# ISM4319.net
KiCad netlist of a schematic drawn in Altium Designer
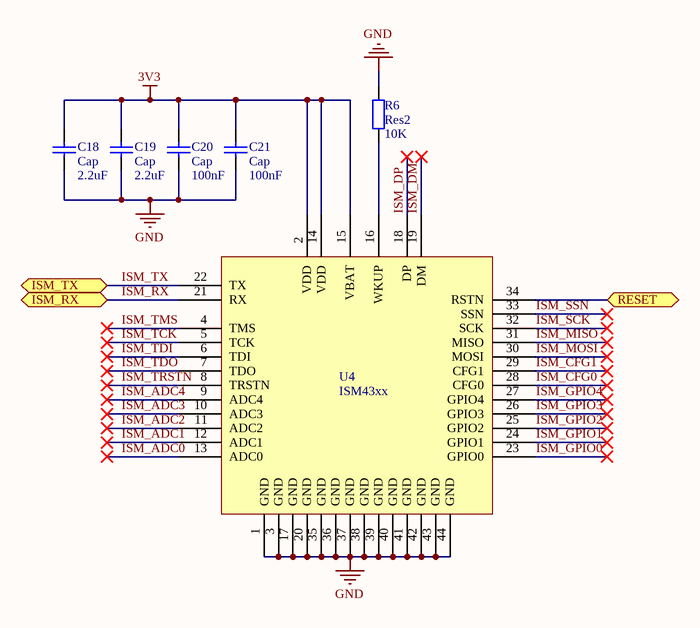
[diagram p0: ISM4319.SchDoc]

(export (version "E")
  (design (tool "Eeschema 10.0.6"))
  (components
    (comp (ref "C18")
      (value "Cap")
      (footprint "0603")
      (description "Capacitor")
      (fields (field (name "ALTIUM_VALUE") "2.2uF"))
      (libsource (lib "Miscellaneous Devices") (part "Cap"))
    )
    (comp (ref "C19")
      (value "Cap")
      (footprint "0603")
      (description "Capacitor")
      (fields (field (name "ALTIUM_VALUE") "2.2uF"))
      (libsource (lib "Miscellaneous Devices") (part "Cap"))
    )
    (comp (ref "C20")
      (value "Cap")
      (footprint "0603")
      (description "Capacitor")
      (fields (field (name "ALTIUM_VALUE") "100nF"))
      (libsource (lib "Miscellaneous Devices") (part "Cap"))
    )
    (comp (ref "C21")
      (value "Cap")
      (footprint "0603")
      (description "Capacitor")
      (fields (field (name "ALTIUM_VALUE") "100nF"))
      (libsource (lib "Miscellaneous Devices") (part "Cap"))
    )
    (comp (ref "R6")
      (value "Res2")
      (footprint "0603")
      (description "Resistor")
      (fields (field (name "ALTIUM_VALUE") "10K"))
      (libsource (lib "Miscellaneous Devices") (part "Res2"))
    )
    (comp (ref "U4")
      (value "ISM43xx")
      (footprint "ISM-WIFI")
      (description "Inventek Systems WiFi Module")
      (libsource (lib "BrewBit") (part "ISM4319"))
    )
  )
  (nets
    (net (code "1") (name "/ISM_ADC0") (class "Default")
      (node (ref "U4") (pin "13") (pinfunction "ADC0_13") (pintype "passive+no_connect"))
    )
    (net (code "2") (name "/ISM_ADC1") (class "Default")
      (node (ref "U4") (pin "12") (pinfunction "ADC1_12") (pintype "passive+no_connect"))
    )
    (net (code "3") (name "/ISM_ADC2") (class "Default")
      (node (ref "U4") (pin "11") (pinfunction "ADC2_11") (pintype "passive+no_connect"))
    )
    (net (code "4") (name "/ISM_ADC3") (class "Default")
      (node (ref "U4") (pin "10") (pinfunction "ADC3_10") (pintype "passive+no_connect"))
    )
    (net (code "5") (name "/ISM_ADC4") (class "Default")
      (node (ref "U4") (pin "9") (pinfunction "ADC4_9") (pintype "passive+no_connect"))
    )
    (net (code "6") (name "/ISM_CFG0") (class "Default")
      (node (ref "U4") (pin "28") (pinfunction "CFG0_28") (pintype "passive+no_connect"))
    )
    (net (code "7") (name "/ISM_CFG1") (class "Default")
      (node (ref "U4") (pin "29") (pinfunction "CFG1_29") (pintype "passive+no_connect"))
    )
    (net (code "8") (name "/ISM_DM") (class "Default")
      (node (ref "U4") (pin "19") (pinfunction "DM_19") (pintype "passive+no_connect"))
    )
    (net (code "9") (name "/ISM_DP") (class "Default")
      (node (ref "U4") (pin "18") (pinfunction "DP_18") (pintype "passive+no_connect"))
    )
    (net (code "10") (name "/ISM_GPIO0") (class "Default")
      (node (ref "U4") (pin "23") (pinfunction "GPIO0_23") (pintype "passive+no_connect"))
    )
    (net (code "11") (name "/ISM_GPIO1") (class "Default")
      (node (ref "U4") (pin "24") (pinfunction "GPIO1_24") (pintype "passive+no_connect"))
    )
    (net (code "12") (name "/ISM_GPIO2") (class "Default")
      (node (ref "U4") (pin "25") (pinfunction "GPIO2_25") (pintype "passive+no_connect"))
    )
    (net (code "13") (name "/ISM_GPIO3") (class "Default")
      (node (ref "U4") (pin "26") (pinfunction "GPIO3_26") (pintype "passive+no_connect"))
    )
    (net (code "14") (name "/ISM_GPIO4") (class "Default")
      (node (ref "U4") (pin "27") (pinfunction "GPIO4_27") (pintype "passive+no_connect"))
    )
    (net (code "15") (name "/ISM_MISO") (class "Default")
      (node (ref "U4") (pin "31") (pinfunction "MISO_31") (pintype "passive+no_connect"))
    )
    (net (code "16") (name "/ISM_MOSI") (class "Default")
      (node (ref "U4") (pin "30") (pinfunction "MOSI_30") (pintype "passive+no_connect"))
    )
    (net (code "17") (name "/ISM_RX") (class "Default")
      (node (ref "U4") (pin "21") (pinfunction "RX_21") (pintype "passive"))
    )
    (net (code "18") (name "/ISM_SCK") (class "Default")
      (node (ref "U4") (pin "32") (pinfunction "SCK_32") (pintype "passive+no_connect"))
    )
    (net (code "19") (name "/ISM_SSN") (class "Default")
      (node (ref "U4") (pin "33") (pinfunction "SSN_33") (pintype "passive+no_connect"))
    )
    (net (code "20") (name "/ISM_TCK") (class "Default")
      (node (ref "U4") (pin "5") (pinfunction "TCK_5") (pintype "passive+no_connect"))
    )
    (net (code "21") (name "/ISM_TDI") (class "Default")
      (node (ref "U4") (pin "6") (pinfunction "TDI_6") (pintype "passive+no_connect"))
    )
    (net (code "22") (name "/ISM_TDO") (class "Default")
      (node (ref "U4") (pin "7") (pinfunction "TDO_7") (pintype "passive+no_connect"))
    )
    (net (code "23") (name "/ISM_TMS") (class "Default")
      (node (ref "U4") (pin "4") (pinfunction "TMS_4") (pintype "passive+no_connect"))
    )
    (net (code "24") (name "/ISM_TRSTN") (class "Default")
      (node (ref "U4") (pin "8") (pinfunction "TRSTN_8") (pintype "passive+no_connect"))
    )
    (net (code "25") (name "/ISM_TX") (class "Default")
      (node (ref "U4") (pin "22") (pinfunction "TX_22") (pintype "passive"))
    )
    (net (code "26") (name "/RESET") (class "Default")
      (node (ref "U4") (pin "34") (pinfunction "RSTN_34") (pintype "passive"))
    )
    (net (code "27") (name "3V3") (class "Default")
      (node (ref "C18") (pin "2") (pinfunction "2_2") (pintype "passive"))
      (node (ref "C19") (pin "2") (pinfunction "2_2") (pintype "passive"))
      (node (ref "C20") (pin "2") (pinfunction "2_2") (pintype "passive"))
      (node (ref "C21") (pin "2") (pinfunction "2_2") (pintype "passive"))
      (node (ref "U4") (pin "14") (pinfunction "VDD_14") (pintype "passive"))
      (node (ref "U4") (pin "15") (pinfunction "VBAT_15") (pintype "passive"))
      (node (ref "U4") (pin "2") (pinfunction "VDD_2") (pintype "passive"))
    )
    (net (code "28") (name "GND") (class "Default")
      (node (ref "C18") (pin "1") (pinfunction "1_1") (pintype "passive"))
      (node (ref "C19") (pin "1") (pinfunction "1_1") (pintype "passive"))
      (node (ref "C20") (pin "1") (pinfunction "1_1") (pintype "passive"))
      (node (ref "C21") (pin "1") (pinfunction "1_1") (pintype "passive"))
      (node (ref "R6") (pin "2") (pinfunction "2_2") (pintype "passive"))
      (node (ref "U4") (pin "1") (pinfunction "GND_1") (pintype "passive"))
      (node (ref "U4") (pin "17") (pinfunction "GND_17") (pintype "passive"))
      (node (ref "U4") (pin "20") (pinfunction "GND_20") (pintype "passive"))
      (node (ref "U4") (pin "3") (pinfunction "GND_3") (pintype "passive"))
      (node (ref "U4") (pin "35") (pinfunction "GND_35") (pintype "passive"))
      (node (ref "U4") (pin "36") (pinfunction "GND_36") (pintype "passive"))
      (node (ref "U4") (pin "37") (pinfunction "GND_37") (pintype "passive"))
      (node (ref "U4") (pin "38") (pinfunction "GND_38") (pintype "passive"))
      (node (ref "U4") (pin "39") (pinfunction "GND_39") (pintype "passive"))
      (node (ref "U4") (pin "40") (pinfunction "GND_40") (pintype "passive"))
      (node (ref "U4") (pin "41") (pinfunction "GND_41") (pintype "passive"))
      (node (ref "U4") (pin "42") (pinfunction "GND_42") (pintype "passive"))
      (node (ref "U4") (pin "43") (pinfunction "GND_43") (pintype "passive"))
      (node (ref "U4") (pin "44") (pinfunction "GND_44") (pintype "passive"))
    )
    (net (code "29") (name "Net-(U4-WKUP)") (class "Default")
      (node (ref "R6") (pin "1") (pinfunction "1_1") (pintype "passive"))
      (node (ref "U4") (pin "16") (pinfunction "WKUP_16") (pintype "passive"))
    )
  )
)
